# MC146818_WiFi.net
KiCad netlist of a schematic drawn in EAGLE
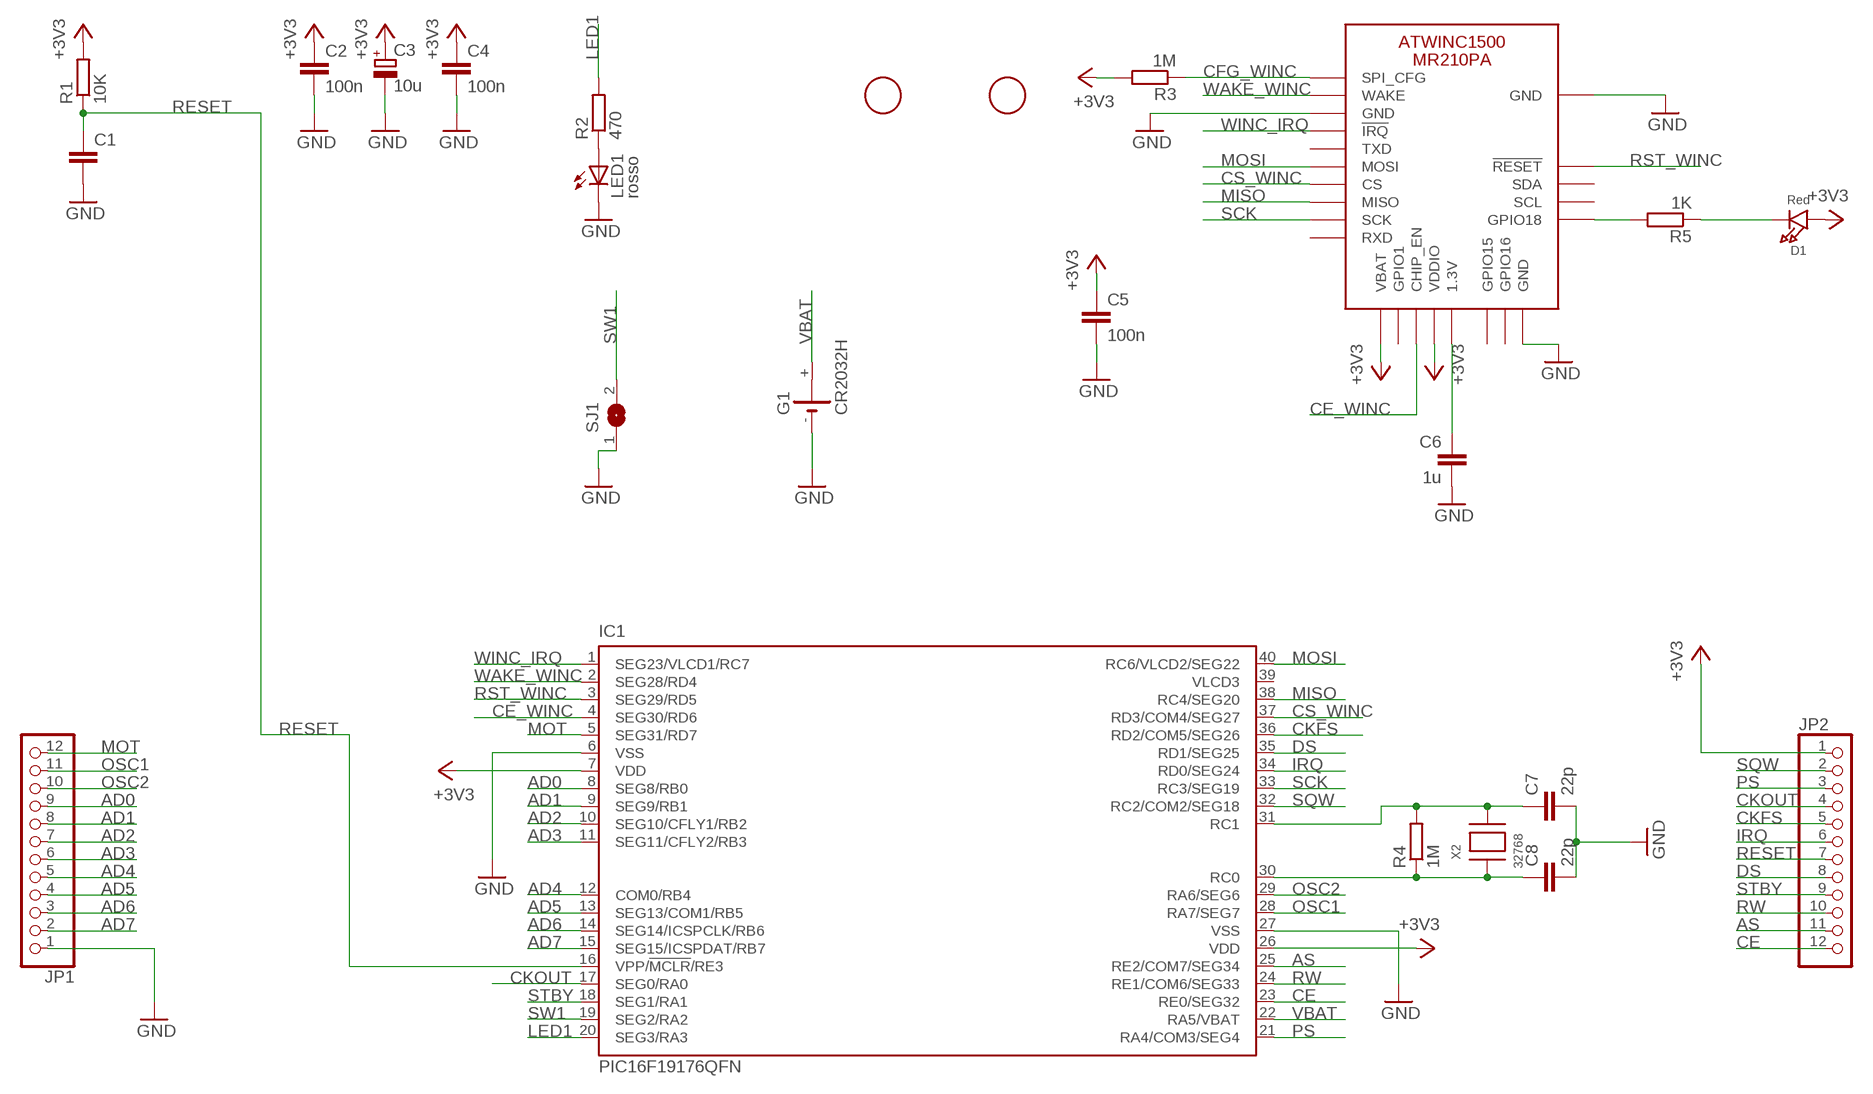
[diagram p0: schematic, sheet 1]

(export (version "E")
  (design (tool "Eeschema 10.0.6"))
  (components
    (comp (ref "C1")
      (value "C-EUC0603")
      (footprint "eagle-import:C0603")
      (libsource (lib "eagle-import") (part "C-EUC0603"))
    )
    (comp (ref "C2")
      (value "100n")
      (footprint "eagle-import:C0603")
      (libsource (lib "eagle-import") (part "C-EUC0603"))
    )
    (comp (ref "C3")
      (value "10u")
      (footprint "eagle-import:SMC_Z")
      (libsource (lib "eagle-import") (part "CPOL-EUSMCZ"))
    )
    (comp (ref "C4")
      (value "100n")
      (footprint "eagle-import:C0603")
      (libsource (lib "eagle-import") (part "C-EUC0603"))
    )
    (comp (ref "C5")
      (value "100n")
      (footprint "eagle-import:C0603")
      (libsource (lib "eagle-import") (part "C-EUC0603"))
    )
    (comp (ref "C6")
      (value "1u")
      (footprint "eagle-import:C0805")
      (libsource (lib "eagle-import") (part "C-EUC0805"))
    )
    (comp (ref "C7")
      (value "22p")
      (footprint "eagle-import:C0603")
      (libsource (lib "eagle-import") (part "C-EUC0603"))
    )
    (comp (ref "C8")
      (value "22p")
      (footprint "eagle-import:C0603")
      (libsource (lib "eagle-import") (part "C-EUC0603"))
    )
    (comp (ref "D1")
      (value "Red")
      (footprint "eagle-import:CHIPLED_0805_NOOUTLINE")
      (libsource (lib "eagle-import") (part "LED0805_NOOUTLINE"))
    )
    (comp (ref "F1")
      (value "FIDUCIAL")
      (footprint "eagle-import:FIDUCIAL_1MM")
      (libsource (lib "eagle-import") (part "FIDUCIAL"))
    )
    (comp (ref "F2")
      (value "FIDUCIAL")
      (footprint "eagle-import:FIDUCIAL_1MM")
      (libsource (lib "eagle-import") (part "FIDUCIAL"))
    )
    (comp (ref "G1")
      (value "CR2032H")
      (footprint "eagle-import:CR2032H")
      (libsource (lib "eagle-import") (part "CR2032H"))
    )
    (comp (ref "IC1")
      (value "PIC16F19176QFN")
      (footprint "eagle-import:UQFN40ML5X5MM")
      (libsource (lib "eagle-import") (part "PIC16F19176QFN"))
    )
    (comp (ref "JP1")
      (value "PINHD-1X12_2.54")
      (footprint "eagle-import:1X12")
      (libsource (lib "eagle-import") (part "PINHD-1X12_2.54"))
    )
    (comp (ref "JP2")
      (value "PINHD-1X12_2.54")
      (footprint "eagle-import:1X12")
      (libsource (lib "eagle-import") (part "PINHD-1X12_2.54"))
    )
    (comp (ref "LED1")
      (value "rosso")
      (footprint "eagle-import:CHIPLED_0805")
      (libsource (lib "eagle-import") (part "LEDCHIPLED_0805"))
    )
    (comp (ref "R1")
      (value "10K")
      (footprint "eagle-import:R0603")
      (libsource (lib "eagle-import") (part "R-EU_R0603"))
    )
    (comp (ref "R2")
      (value "470")
      (footprint "eagle-import:R0603")
      (libsource (lib "eagle-import") (part "R-EU_R0603"))
    )
    (comp (ref "R3")
      (value "1M")
      (footprint "eagle-import:R0603")
      (libsource (lib "eagle-import") (part "R-EU_R0603"))
    )
    (comp (ref "R4")
      (value "1M")
      (footprint "eagle-import:R0603")
      (libsource (lib "eagle-import") (part "R-EU_R0603"))
    )
    (comp (ref "R5")
      (value "1K")
      (footprint "eagle-import:R0603")
      (libsource (lib "eagle-import") (part "R-EU_R0603"))
    )
    (comp (ref "SJ1") (value "SJ") (footprint "eagle-import:SJ") (libsource (lib "eagle-import") (part "SJ")))
    (comp (ref "X1")
      (value "ATWINC1500_MR210PB")
      (footprint "eagle-import:ATWINC1500_MR210PA")
      (libsource (lib "eagle-import") (part "ATWINC1500_MR210PA"))
    )
    (comp (ref "X2")
      (value "32768")
      (footprint "eagle-import:XTAL3215")
      (libsource (lib "eagle-import") (part "XTAL-3.2X1.5"))
    )
  )
  (nets
    (net (code "1") (name "+3V3") (class "Default")
      (node (ref "C2") (pin "1") (pinfunction "1_1") (pintype "passive"))
      (node (ref "C3") (pin "+") (pinfunction "+_+") (pintype "passive"))
      (node (ref "C4") (pin "1") (pinfunction "1_1") (pintype "passive"))
      (node (ref "C5") (pin "1") (pinfunction "1_1") (pintype "passive"))
      (node (ref "D1") (pin "A") (pinfunction "A_A") (pintype "passive"))
      (node (ref "IC1") (pin "26") (pinfunction "VDD_26") (pintype "power_in"))
      (node (ref "IC1") (pin "7") (pinfunction "VDD_7") (pintype "power_in"))
      (node (ref "JP2") (pin "1") (pinfunction "1_1") (pintype "passive"))
      (node (ref "R1") (pin "2") (pinfunction "2_2") (pintype "passive"))
      (node (ref "R3") (pin "2") (pinfunction "2_2") (pintype "passive"))
      (node (ref "X1") (pin "J20") (pinfunction "VBAT_J20") (pintype "power_in"))
      (node (ref "X1") (pin "J23") (pinfunction "VDDIO_J23") (pintype "power_in"))
    )
    (net (code "2") (name "/AD0") (class "Default")
      (node (ref "IC1") (pin "8") (pinfunction "SEG8/RB0_8") (pintype "bidirectional"))
      (node (ref "JP1") (pin "9") (pinfunction "9_9") (pintype "passive"))
    )
    (net (code "3") (name "/AD1") (class "Default")
      (node (ref "IC1") (pin "9") (pinfunction "SEG9/RB1_9") (pintype "bidirectional"))
      (node (ref "JP1") (pin "8") (pinfunction "8_8") (pintype "passive"))
    )
    (net (code "4") (name "/AD2") (class "Default")
      (node (ref "IC1") (pin "10") (pinfunction "SEG10/CFLY1/RB2_10") (pintype "bidirectional"))
      (node (ref "JP1") (pin "7") (pinfunction "7_7") (pintype "passive"))
    )
    (net (code "5") (name "/AD3") (class "Default")
      (node (ref "IC1") (pin "11") (pinfunction "SEG11/CFLY2/RB3_11") (pintype "bidirectional"))
      (node (ref "JP1") (pin "6") (pinfunction "6_6") (pintype "passive"))
    )
    (net (code "6") (name "/AD4") (class "Default")
      (node (ref "IC1") (pin "12") (pinfunction "COM0/RB4_12") (pintype "bidirectional"))
      (node (ref "JP1") (pin "5") (pinfunction "5_5") (pintype "passive"))
    )
    (net (code "7") (name "/AD5") (class "Default")
      (node (ref "IC1") (pin "13") (pinfunction "SEG13/COM1/RB5_13") (pintype "bidirectional"))
      (node (ref "JP1") (pin "4") (pinfunction "4_4") (pintype "passive"))
    )
    (net (code "8") (name "/AD6") (class "Default")
      (node (ref "IC1") (pin "14") (pinfunction "SEG14/ICSPCLK/RB6_14") (pintype "bidirectional"))
      (node (ref "JP1") (pin "3") (pinfunction "3_3") (pintype "passive"))
    )
    (net (code "9") (name "/AD7") (class "Default")
      (node (ref "IC1") (pin "15") (pinfunction "SEG15/ICSPDAT/RB7_15") (pintype "bidirectional"))
      (node (ref "JP1") (pin "2") (pinfunction "2_2") (pintype "passive"))
    )
    (net (code "10") (name "/AS") (class "Default")
      (node (ref "IC1") (pin "25") (pinfunction "RE2/COM7/SEG34_25") (pintype "bidirectional"))
      (node (ref "JP2") (pin "11") (pinfunction "11_11") (pintype "passive"))
    )
    (net (code "11") (name "/CE") (class "Default")
      (node (ref "IC1") (pin "23") (pinfunction "RE0/SEG32_23") (pintype "bidirectional"))
      (node (ref "JP2") (pin "12") (pinfunction "12_12") (pintype "passive"))
    )
    (net (code "12") (name "/CE_WINC") (class "Default")
      (node (ref "IC1") (pin "4") (pinfunction "SEG30/RD6_4") (pintype "bidirectional"))
      (node (ref "X1") (pin "J22") (pinfunction "CHIP_EN_J22") (pintype "input"))
    )
    (net (code "13") (name "/CFG_WINC") (class "Default")
      (node (ref "R3") (pin "1") (pinfunction "1_1") (pintype "passive"))
      (node (ref "X1") (pin "J10") (pinfunction "SPI_CFG_J10") (pintype "input"))
    )
    (net (code "14") (name "/CKFS") (class "Default")
      (node (ref "IC1") (pin "36") (pinfunction "RD2/COM5/SEG26_36") (pintype "bidirectional"))
      (node (ref "JP2") (pin "5") (pinfunction "5_5") (pintype "passive"))
    )
    (net (code "15") (name "/CKOUT") (class "Default")
      (node (ref "IC1") (pin "17") (pinfunction "SEG0/RA0_17") (pintype "bidirectional"))
      (node (ref "JP2") (pin "4") (pinfunction "4_4") (pintype "passive"))
    )
    (net (code "16") (name "/CS_WINC") (class "Default")
      (node (ref "IC1") (pin "37") (pinfunction "RD3/COM4/SEG27_37") (pintype "bidirectional"))
      (node (ref "X1") (pin "J16") (pinfunction "CS_J16") (pintype "input"))
    )
    (net (code "17") (name "/DS") (class "Default")
      (node (ref "IC1") (pin "35") (pinfunction "RD1/SEG25_35") (pintype "bidirectional"))
      (node (ref "JP2") (pin "8") (pinfunction "8_8") (pintype "passive"))
    )
    (net (code "18") (name "/IRQ") (class "Default")
      (node (ref "IC1") (pin "34") (pinfunction "RD0/SEG24_34") (pintype "bidirectional"))
      (node (ref "JP2") (pin "6") (pinfunction "6_6") (pintype "passive"))
    )
    (net (code "19") (name "/LED1") (class "Default")
      (node (ref "IC1") (pin "20") (pinfunction "SEG3/RA3_20") (pintype "bidirectional"))
      (node (ref "R2") (pin "2") (pinfunction "2_2") (pintype "passive"))
    )
    (net (code "20") (name "/MISO") (class "Default")
      (node (ref "IC1") (pin "38") (pinfunction "RC4/SEG20_38") (pintype "bidirectional"))
      (node (ref "X1") (pin "J17") (pinfunction "MISO_J17") (pintype "output"))
    )
    (net (code "21") (name "/MOSI") (class "Default")
      (node (ref "IC1") (pin "40") (pinfunction "RC6/VLCD2/SEG22_40") (pintype "bidirectional"))
      (node (ref "X1") (pin "J15") (pinfunction "MOSI_J15") (pintype "input"))
    )
    (net (code "22") (name "/MOT") (class "Default")
      (node (ref "IC1") (pin "5") (pinfunction "SEG31/RD7_5") (pintype "bidirectional"))
      (node (ref "JP1") (pin "12") (pinfunction "12_12") (pintype "passive"))
    )
    (net (code "23") (name "/OSC1") (class "Default")
      (node (ref "IC1") (pin "28") (pinfunction "RA7/SEG7_28") (pintype "bidirectional"))
      (node (ref "JP1") (pin "11") (pinfunction "11_11") (pintype "passive"))
    )
    (net (code "24") (name "/OSC2") (class "Default")
      (node (ref "IC1") (pin "29") (pinfunction "RA6/SEG6_29") (pintype "bidirectional"))
      (node (ref "JP1") (pin "10") (pinfunction "10_10") (pintype "passive"))
    )
    (net (code "25") (name "/PS") (class "Default")
      (node (ref "IC1") (pin "21") (pinfunction "RA4/COM3/SEG4_21") (pintype "bidirectional"))
      (node (ref "JP2") (pin "3") (pinfunction "3_3") (pintype "passive"))
    )
    (net (code "26") (name "/RESET") (class "Default")
      (node (ref "C1") (pin "1") (pinfunction "1_1") (pintype "passive"))
      (node (ref "IC1") (pin "16") (pinfunction "VPP/~{MCLR}/RE3_16") (pintype "input"))
      (node (ref "JP2") (pin "7") (pinfunction "7_7") (pintype "passive"))
      (node (ref "R1") (pin "1") (pinfunction "1_1") (pintype "passive"))
    )
    (net (code "27") (name "/RST_WINC") (class "Default")
      (node (ref "IC1") (pin "3") (pinfunction "SEG29/RD5_3") (pintype "bidirectional"))
      (node (ref "X1") (pin "J4") (pinfunction "~{RESET}_J4") (pintype "input"))
    )
    (net (code "28") (name "/RW") (class "Default")
      (node (ref "IC1") (pin "24") (pinfunction "RE1/COM6/SEG33_24") (pintype "bidirectional"))
      (node (ref "JP2") (pin "10") (pinfunction "10_10") (pintype "passive"))
    )
    (net (code "29") (name "/SCK") (class "Default")
      (node (ref "IC1") (pin "33") (pinfunction "RC3/SEG19_33") (pintype "bidirectional"))
      (node (ref "X1") (pin "J18") (pinfunction "SCK_J18") (pintype "input"))
    )
    (net (code "30") (name "/SQW") (class "Default")
      (node (ref "IC1") (pin "32") (pinfunction "RC2/COM2/SEG18_32") (pintype "bidirectional"))
      (node (ref "JP2") (pin "2") (pinfunction "2_2") (pintype "passive"))
    )
    (net (code "31") (name "/STBY") (class "Default")
      (node (ref "IC1") (pin "18") (pinfunction "SEG1/RA1_18") (pintype "bidirectional"))
      (node (ref "JP2") (pin "9") (pinfunction "9_9") (pintype "passive"))
    )
    (net (code "32") (name "/SW1") (class "Default")
      (node (ref "IC1") (pin "19") (pinfunction "SEG2/RA2_19") (pintype "bidirectional"))
      (node (ref "SJ1") (pin "2") (pinfunction "2_2") (pintype "passive"))
    )
    (net (code "33") (name "/VBAT") (class "Default")
      (node (ref "G1") (pin "+") (pinfunction "+_+") (pintype "passive"))
      (node (ref "IC1") (pin "22") (pinfunction "RA5/VBAT_22") (pintype "bidirectional"))
    )
    (net (code "34") (name "/WAKE_WINC") (class "Default")
      (node (ref "IC1") (pin "2") (pinfunction "SEG28/RD4_2") (pintype "bidirectional"))
      (node (ref "X1") (pin "J11") (pinfunction "WAKE_J11") (pintype "input"))
    )
    (net (code "35") (name "/WINC_IRQ") (class "Default")
      (node (ref "IC1") (pin "1") (pinfunction "SEG23/VLCD1/RC7_1") (pintype "bidirectional"))
      (node (ref "X1") (pin "J13") (pinfunction "~{IRQ}_J13") (pintype "output"))
    )
    (net (code "36") (name "GND") (class "Default")
      (node (ref "C1") (pin "2") (pinfunction "2_2") (pintype "passive"))
      (node (ref "C2") (pin "2") (pinfunction "2_2") (pintype "passive"))
      (node (ref "C3") (pin "-") (pinfunction "-_-") (pintype "passive"))
      (node (ref "C4") (pin "2") (pinfunction "2_2") (pintype "passive"))
      (node (ref "C5") (pin "2") (pinfunction "2_2") (pintype "passive"))
      (node (ref "C6") (pin "2") (pinfunction "2_2") (pintype "passive"))
      (node (ref "C7") (pin "2") (pinfunction "2_2") (pintype "passive"))
      (node (ref "C8") (pin "2") (pinfunction "2_2") (pintype "passive"))
      (node (ref "G1") (pin "-") (pinfunction "-_-") (pintype "passive"))
      (node (ref "IC1") (pin "27") (pinfunction "VSS_27") (pintype "power_in"))
      (node (ref "IC1") (pin "6") (pinfunction "VSS_6") (pintype "power_in"))
      (node (ref "JP1") (pin "1") (pinfunction "1_1") (pintype "passive"))
      (node (ref "LED1") (pin "C") (pinfunction "C_C") (pintype "passive"))
      (node (ref "SJ1") (pin "1") (pinfunction "1_1") (pintype "passive"))
      (node (ref "X1") (pin "J12") (pinfunction "GND_J12") (pintype "power_in"))
      (node (ref "X1") (pin "J28") (pinfunction "GND_J28") (pintype "power_in"))
      (node (ref "X1") (pin "J9") (pinfunction "GND_J9") (pintype "bidirectional"))
      (node (ref "X1") (pin "MTGND") (pinfunction "GND_MTGND") (pintype "power_in"))
    )
    (net (code "37") (name "Net-(D1-PadC)") (class "Default")
      (node (ref "D1") (pin "C") (pinfunction "C_C") (pintype "passive"))
      (node (ref "R5") (pin "1") (pinfunction "1_1") (pintype "passive"))
    )
    (net (code "38") (name "Net-(IC1-RC0)") (class "Default")
      (node (ref "C8") (pin "1") (pinfunction "1_1") (pintype "passive"))
      (node (ref "IC1") (pin "30") (pinfunction "RC0_30") (pintype "bidirectional"))
      (node (ref "R4") (pin "1") (pinfunction "1_1") (pintype "passive"))
      (node (ref "X2") (pin "P$1") (pinfunction "P$1_P$1") (pintype "bidirectional"))
    )
    (net (code "39") (name "Net-(IC1-RC1)") (class "Default")
      (node (ref "C7") (pin "1") (pinfunction "1_1") (pintype "passive"))
      (node (ref "IC1") (pin "31") (pinfunction "RC1_31") (pintype "bidirectional"))
      (node (ref "R4") (pin "2") (pinfunction "2_2") (pintype "passive"))
      (node (ref "X2") (pin "P$2") (pinfunction "P$2_P$2") (pintype "bidirectional"))
    )
    (net (code "40") (name "Net-(LED1-PadA)") (class "Default")
      (node (ref "LED1") (pin "A") (pinfunction "A_A") (pintype "passive"))
      (node (ref "R2") (pin "1") (pinfunction "1_1") (pintype "passive"))
    )
    (net (code "41") (name "Net-(X1-1.3V)") (class "Default")
      (node (ref "C6") (pin "1") (pinfunction "1_1") (pintype "passive"))
      (node (ref "X1") (pin "J24") (pinfunction "1.3V_J24") (pintype "passive"))
    )
    (net (code "42") (name "Net-(X1-GPIO18)") (class "Default")
      (node (ref "R5") (pin "2") (pinfunction "2_2") (pintype "passive"))
      (node (ref "X1") (pin "J1") (pinfunction "GPIO18_J1") (pintype "bidirectional"))
    )
    (net (code "43") (name "unconnected-(G1-+-Pad+@1)") (class "Default")
      (node (ref "G1") (pin "+@1") (pinfunction "+_+@1") (pintype "passive"))
    )
    (net (code "44") (name "unconnected-(IC1-VLCD3-Pad39)") (class "Default")
      (node (ref "IC1") (pin "39") (pinfunction "VLCD3_39") (pintype "bidirectional"))
    )
    (net (code "45") (name "unconnected-(X1-GPIO1-PadJ21)") (class "Default")
      (node (ref "X1") (pin "J21") (pinfunction "GPIO1_J21") (pintype "bidirectional"))
    )
    (net (code "46") (name "unconnected-(X1-GPIO15-PadJ26)") (class "Default")
      (node (ref "X1") (pin "J26") (pinfunction "GPIO15_J26") (pintype "bidirectional"))
    )
    (net (code "47") (name "unconnected-(X1-GPIO16-PadJ27)") (class "Default")
      (node (ref "X1") (pin "J27") (pinfunction "GPIO16_J27") (pintype "bidirectional"))
    )
    (net (code "48") (name "unconnected-(X1-RXD-PadJ19)") (class "Default")
      (node (ref "X1") (pin "J19") (pinfunction "RXD_J19") (pintype "input"))
    )
    (net (code "49") (name "unconnected-(X1-SCL-PadJ2)") (class "Default")
      (node (ref "X1") (pin "J2") (pinfunction "SCL_J2") (pintype "bidirectional"))
    )
    (net (code "50") (name "unconnected-(X1-SDA-PadJ3)") (class "Default")
      (node (ref "X1") (pin "J3") (pinfunction "SDA_J3") (pintype "bidirectional"))
    )
    (net (code "51") (name "unconnected-(X1-TXD-PadJ14)") (class "Default")
      (node (ref "X1") (pin "J14") (pinfunction "TXD_J14") (pintype "output"))
    )
  )
)
